# Serwo.net
KiCad netlist of a schematic drawn in Altium Designer
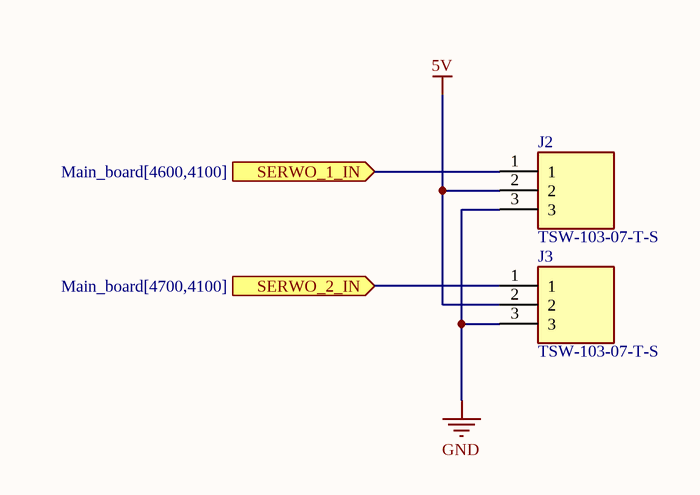
[diagram p0: Serwo.SchDoc]

(export (version "E")
  (design (tool "Eeschema 10.0.6"))
  (components
    (comp (ref "J2")
      (value "TSW-103-07-T-S")
      (footprint "PCB 3 PIN PADS")
      (description "Connector")
      (fields (field (name "MOUSER PART NUMBER") "200-TSW10307TS"))
      (libsource (lib "SamacSys") (part "TSW-103-07-T-S"))
    )
    (comp (ref "J3")
      (value "TSW-103-07-T-S")
      (footprint "PCB 3 PIN PADS")
      (description "Connector")
      (fields (field (name "MOUSER PART NUMBER") "200-TSW10307TS"))
      (libsource (lib "SamacSys") (part "TSW-103-07-T-S"))
    )
  )
  (nets
    (net (code "1") (name "/SERWO_1_IN") (class "Default")
      (node (ref "J2") (pin "1") (pinfunction "1_1") (pintype "passive"))
    )
    (net (code "2") (name "/SERWO_2_IN") (class "Default")
      (node (ref "J3") (pin "1") (pinfunction "1_1") (pintype "passive"))
    )
    (net (code "3") (name "5V") (class "Default")
      (node (ref "J2") (pin "2") (pinfunction "2_2") (pintype "passive"))
      (node (ref "J3") (pin "2") (pinfunction "2_2") (pintype "passive"))
    )
    (net (code "4") (name "GND") (class "Default")
      (node (ref "J2") (pin "3") (pinfunction "3_3") (pintype "passive"))
      (node (ref "J3") (pin "3") (pinfunction "3_3") (pintype "passive"))
    )
  )
)
